# keypad.net
KiCad netlist of a schematic drawn in Altium Designer
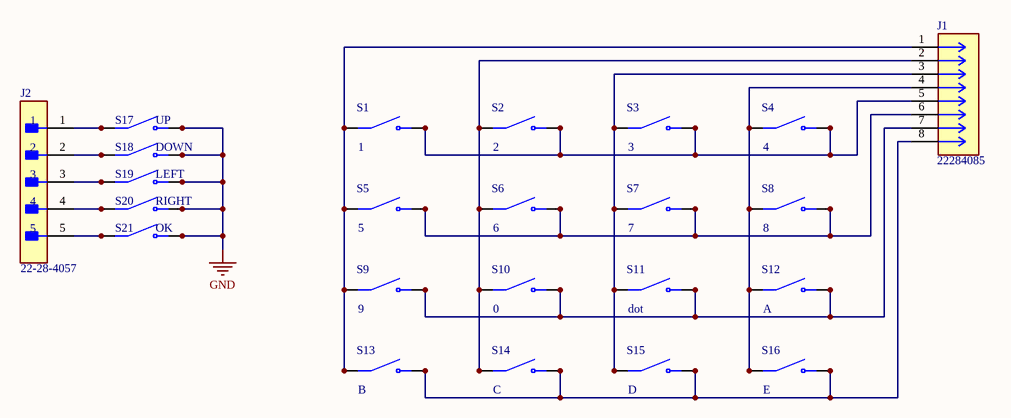
[diagram p0: keypad.SchDoc]

(export (version "E")
  (design (tool "Eeschema 10.0.6"))
  (components
    (comp (ref "J1")
      (value "22284085")
      (footprint "CONN_SD-42375-001_M295_08_MOL")
      (libsource (lib "Achintha Bandara") (part "22284085"))
    )
    (comp (ref "J2")
      (value "22-28-4057")
      (footprint "FP-22-28-4057-MFG")
      (description "KK 100 HDR ASSY BKWY 05 CKT 30 S")
      (libsource (lib "Altium Content Vault") (part "bf93c07fd2649a848d0ec8585582aab"))
    )
    (comp (ref "S1")
      (value "1")
      (footprint "SW_B3F-4050")
      (description "Tactile Switch SPST-NO Top Actuated Through Hole")
      (fields (field (name "MP") "B3F-4050") (field (name "MF") "Omron Electronics"))
      (libsource (lib "Achintha Bandara") (part "B3F-4050"))
    )
    (comp (ref "S2")
      (value "2")
      (footprint "SW_B3F-4050")
      (description "Tactile Switch SPST-NO Top Actuated Through Hole")
      (fields (field (name "MP") "B3F-4050") (field (name "MF") "Omron Electronics"))
      (libsource (lib "Achintha Bandara") (part "B3F-4050"))
    )
    (comp (ref "S3")
      (value "3")
      (footprint "SW_B3F-4050")
      (description "Tactile Switch SPST-NO Top Actuated Through Hole")
      (fields (field (name "MP") "B3F-4050") (field (name "MF") "Omron Electronics"))
      (libsource (lib "Achintha Bandara") (part "B3F-4050"))
    )
    (comp (ref "S4")
      (value "4")
      (footprint "SW_B3F-4050")
      (description "Tactile Switch SPST-NO Top Actuated Through Hole")
      (fields (field (name "MP") "B3F-4050") (field (name "MF") "Omron Electronics"))
      (libsource (lib "Achintha Bandara") (part "B3F-4050"))
    )
    (comp (ref "S5")
      (value "5")
      (footprint "SW_B3F-4050")
      (description "Tactile Switch SPST-NO Top Actuated Through Hole")
      (fields (field (name "MP") "B3F-4050") (field (name "MF") "Omron Electronics"))
      (libsource (lib "Achintha Bandara") (part "B3F-4050"))
    )
    (comp (ref "S6")
      (value "6")
      (footprint "SW_B3F-4050")
      (description "Tactile Switch SPST-NO Top Actuated Through Hole")
      (fields (field (name "MP") "B3F-4050") (field (name "MF") "Omron Electronics"))
      (libsource (lib "Achintha Bandara") (part "B3F-4050"))
    )
    (comp (ref "S7")
      (value "7")
      (footprint "SW_B3F-4050")
      (description "Tactile Switch SPST-NO Top Actuated Through Hole")
      (fields (field (name "MP") "B3F-4050") (field (name "MF") "Omron Electronics"))
      (libsource (lib "Achintha Bandara") (part "B3F-4050"))
    )
    (comp (ref "S8")
      (value "8")
      (footprint "SW_B3F-4050")
      (description "Tactile Switch SPST-NO Top Actuated Through Hole")
      (fields (field (name "MP") "B3F-4050") (field (name "MF") "Omron Electronics"))
      (libsource (lib "Achintha Bandara") (part "B3F-4050"))
    )
    (comp (ref "S9")
      (value "9")
      (footprint "SW_B3F-4050")
      (description "Tactile Switch SPST-NO Top Actuated Through Hole")
      (fields (field (name "MP") "B3F-4050") (field (name "MF") "Omron Electronics"))
      (libsource (lib "Achintha Bandara") (part "B3F-4050"))
    )
    (comp (ref "S10")
      (value "0")
      (footprint "SW_B3F-4050")
      (description "Tactile Switch SPST-NO Top Actuated Through Hole")
      (fields (field (name "MP") "B3F-4050") (field (name "MF") "Omron Electronics"))
      (libsource (lib "Achintha Bandara") (part "B3F-4050"))
    )
    (comp (ref "S11")
      (value "dot")
      (footprint "SW_B3F-4050")
      (description "Tactile Switch SPST-NO Top Actuated Through Hole")
      (fields (field (name "MP") "B3F-4050") (field (name "MF") "Omron Electronics"))
      (libsource (lib "Achintha Bandara") (part "B3F-4050"))
    )
    (comp (ref "S12")
      (value "A")
      (footprint "SW_B3F-4050")
      (description "Tactile Switch SPST-NO Top Actuated Through Hole")
      (fields (field (name "MP") "B3F-4050") (field (name "MF") "Omron Electronics"))
      (libsource (lib "Achintha Bandara") (part "B3F-4050"))
    )
    (comp (ref "S13")
      (value "B")
      (footprint "SW_B3F-4050")
      (description "Tactile Switch SPST-NO Top Actuated Through Hole")
      (fields (field (name "MP") "B3F-4050") (field (name "MF") "Omron Electronics"))
      (libsource (lib "Achintha Bandara") (part "B3F-4050"))
    )
    (comp (ref "S14")
      (value "C")
      (footprint "SW_B3F-4050")
      (description "Tactile Switch SPST-NO Top Actuated Through Hole")
      (fields (field (name "MP") "B3F-4050") (field (name "MF") "Omron Electronics"))
      (libsource (lib "Achintha Bandara") (part "B3F-4050"))
    )
    (comp (ref "S15")
      (value "D")
      (footprint "SW_B3F-4050")
      (description "Tactile Switch SPST-NO Top Actuated Through Hole")
      (fields (field (name "MP") "B3F-4050") (field (name "MF") "Omron Electronics"))
      (libsource (lib "Achintha Bandara") (part "B3F-4050"))
    )
    (comp (ref "S16")
      (value "E")
      (footprint "SW_B3F-4050")
      (description "Tactile Switch SPST-NO Top Actuated Through Hole")
      (fields (field (name "MP") "B3F-4050") (field (name "MF") "Omron Electronics"))
      (libsource (lib "Achintha Bandara") (part "B3F-4050"))
    )
    (comp (ref "S17")
      (value "UP")
      (footprint "SW_B3F-4050")
      (description "Tactile Switch SPST-NO Top Actuated Through Hole")
      (fields (field (name "MP") "B3F-4050") (field (name "MF") "Omron Electronics"))
      (libsource (lib "Achintha Bandara") (part "B3F-4050"))
    )
    (comp (ref "S18")
      (value "DOWN")
      (footprint "SW_B3F-4050")
      (description "Tactile Switch SPST-NO Top Actuated Through Hole")
      (fields (field (name "MP") "B3F-4050") (field (name "MF") "Omron Electronics"))
      (libsource (lib "Achintha Bandara") (part "B3F-4050"))
    )
    (comp (ref "S19")
      (value "LEFT")
      (footprint "SW_B3F-4050")
      (description "Tactile Switch SPST-NO Top Actuated Through Hole")
      (fields (field (name "MP") "B3F-4050") (field (name "MF") "Omron Electronics"))
      (libsource (lib "Achintha Bandara") (part "B3F-4050"))
    )
    (comp (ref "S20")
      (value "RIGHT")
      (footprint "SW_B3F-4050")
      (description "Tactile Switch SPST-NO Top Actuated Through Hole")
      (fields (field (name "MP") "B3F-4050") (field (name "MF") "Omron Electronics"))
      (libsource (lib "Achintha Bandara") (part "B3F-4050"))
    )
    (comp (ref "S21")
      (value "OK")
      (footprint "SW_B3F-4050")
      (description "Tactile Switch SPST-NO Top Actuated Through Hole")
      (fields (field (name "MP") "B3F-4050") (field (name "MF") "Omron Electronics"))
      (libsource (lib "Achintha Bandara") (part "B3F-4050"))
    )
  )
  (nets
    (net (code "1") (name "GND") (class "Default")
      (node (ref "S17") (pin "3") (pinfunction "NO_3") (pintype "passive"))
      (node (ref "S17") (pin "4") (pinfunction "NO_4") (pintype "passive"))
      (node (ref "S18") (pin "3") (pinfunction "NO_3") (pintype "passive"))
      (node (ref "S18") (pin "4") (pinfunction "NO_4") (pintype "passive"))
      (node (ref "S19") (pin "3") (pinfunction "NO_3") (pintype "passive"))
      (node (ref "S19") (pin "4") (pinfunction "NO_4") (pintype "passive"))
      (node (ref "S20") (pin "3") (pinfunction "NO_3") (pintype "passive"))
      (node (ref "S20") (pin "4") (pinfunction "NO_4") (pintype "passive"))
      (node (ref "S21") (pin "3") (pinfunction "NO_3") (pintype "passive"))
      (node (ref "S21") (pin "4") (pinfunction "NO_4") (pintype "passive"))
    )
    (net (code "2") (name "Net-(J1-Pad1)") (class "Default")
      (node (ref "J1") (pin "1") (pinfunction "1_1") (pintype "passive"))
      (node (ref "S1") (pin "1") (pinfunction "COM_1") (pintype "passive"))
      (node (ref "S1") (pin "2") (pinfunction "COM_2") (pintype "passive"))
      (node (ref "S13") (pin "1") (pinfunction "COM_1") (pintype "passive"))
      (node (ref "S13") (pin "2") (pinfunction "COM_2") (pintype "passive"))
      (node (ref "S5") (pin "1") (pinfunction "COM_1") (pintype "passive"))
      (node (ref "S5") (pin "2") (pinfunction "COM_2") (pintype "passive"))
      (node (ref "S9") (pin "1") (pinfunction "COM_1") (pintype "passive"))
      (node (ref "S9") (pin "2") (pinfunction "COM_2") (pintype "passive"))
    )
    (net (code "3") (name "Net-(J1-Pad2)") (class "Default")
      (node (ref "J1") (pin "2") (pinfunction "2_2") (pintype "passive"))
      (node (ref "S10") (pin "1") (pinfunction "COM_1") (pintype "passive"))
      (node (ref "S10") (pin "2") (pinfunction "COM_2") (pintype "passive"))
      (node (ref "S14") (pin "1") (pinfunction "COM_1") (pintype "passive"))
      (node (ref "S14") (pin "2") (pinfunction "COM_2") (pintype "passive"))
      (node (ref "S2") (pin "1") (pinfunction "COM_1") (pintype "passive"))
      (node (ref "S2") (pin "2") (pinfunction "COM_2") (pintype "passive"))
      (node (ref "S6") (pin "1") (pinfunction "COM_1") (pintype "passive"))
      (node (ref "S6") (pin "2") (pinfunction "COM_2") (pintype "passive"))
    )
    (net (code "4") (name "Net-(J1-Pad3)") (class "Default")
      (node (ref "J1") (pin "3") (pinfunction "3_3") (pintype "passive"))
      (node (ref "S11") (pin "1") (pinfunction "COM_1") (pintype "passive"))
      (node (ref "S11") (pin "2") (pinfunction "COM_2") (pintype "passive"))
      (node (ref "S15") (pin "1") (pinfunction "COM_1") (pintype "passive"))
      (node (ref "S15") (pin "2") (pinfunction "COM_2") (pintype "passive"))
      (node (ref "S3") (pin "1") (pinfunction "COM_1") (pintype "passive"))
      (node (ref "S3") (pin "2") (pinfunction "COM_2") (pintype "passive"))
      (node (ref "S7") (pin "1") (pinfunction "COM_1") (pintype "passive"))
      (node (ref "S7") (pin "2") (pinfunction "COM_2") (pintype "passive"))
    )
    (net (code "5") (name "Net-(J1-Pad4)") (class "Default")
      (node (ref "J1") (pin "4") (pinfunction "4_4") (pintype "passive"))
      (node (ref "S12") (pin "1") (pinfunction "COM_1") (pintype "passive"))
      (node (ref "S12") (pin "2") (pinfunction "COM_2") (pintype "passive"))
      (node (ref "S16") (pin "1") (pinfunction "COM_1") (pintype "passive"))
      (node (ref "S16") (pin "2") (pinfunction "COM_2") (pintype "passive"))
      (node (ref "S4") (pin "1") (pinfunction "COM_1") (pintype "passive"))
      (node (ref "S4") (pin "2") (pinfunction "COM_2") (pintype "passive"))
      (node (ref "S8") (pin "1") (pinfunction "COM_1") (pintype "passive"))
      (node (ref "S8") (pin "2") (pinfunction "COM_2") (pintype "passive"))
    )
    (net (code "6") (name "Net-(J1-Pad5)") (class "Default")
      (node (ref "J1") (pin "5") (pinfunction "5_5") (pintype "passive"))
      (node (ref "S1") (pin "3") (pinfunction "NO_3") (pintype "passive"))
      (node (ref "S1") (pin "4") (pinfunction "NO_4") (pintype "passive"))
      (node (ref "S2") (pin "3") (pinfunction "NO_3") (pintype "passive"))
      (node (ref "S2") (pin "4") (pinfunction "NO_4") (pintype "passive"))
      (node (ref "S3") (pin "3") (pinfunction "NO_3") (pintype "passive"))
      (node (ref "S3") (pin "4") (pinfunction "NO_4") (pintype "passive"))
      (node (ref "S4") (pin "3") (pinfunction "NO_3") (pintype "passive"))
      (node (ref "S4") (pin "4") (pinfunction "NO_4") (pintype "passive"))
    )
    (net (code "7") (name "Net-(J1-Pad6)") (class "Default")
      (node (ref "J1") (pin "6") (pinfunction "6_6") (pintype "passive"))
      (node (ref "S5") (pin "3") (pinfunction "NO_3") (pintype "passive"))
      (node (ref "S5") (pin "4") (pinfunction "NO_4") (pintype "passive"))
      (node (ref "S6") (pin "3") (pinfunction "NO_3") (pintype "passive"))
      (node (ref "S6") (pin "4") (pinfunction "NO_4") (pintype "passive"))
      (node (ref "S7") (pin "3") (pinfunction "NO_3") (pintype "passive"))
      (node (ref "S7") (pin "4") (pinfunction "NO_4") (pintype "passive"))
      (node (ref "S8") (pin "3") (pinfunction "NO_3") (pintype "passive"))
      (node (ref "S8") (pin "4") (pinfunction "NO_4") (pintype "passive"))
    )
    (net (code "8") (name "Net-(J1-Pad7)") (class "Default")
      (node (ref "J1") (pin "7") (pinfunction "7_7") (pintype "passive"))
      (node (ref "S10") (pin "3") (pinfunction "NO_3") (pintype "passive"))
      (node (ref "S10") (pin "4") (pinfunction "NO_4") (pintype "passive"))
      (node (ref "S11") (pin "3") (pinfunction "NO_3") (pintype "passive"))
      (node (ref "S11") (pin "4") (pinfunction "NO_4") (pintype "passive"))
      (node (ref "S12") (pin "3") (pinfunction "NO_3") (pintype "passive"))
      (node (ref "S12") (pin "4") (pinfunction "NO_4") (pintype "passive"))
      (node (ref "S9") (pin "3") (pinfunction "NO_3") (pintype "passive"))
      (node (ref "S9") (pin "4") (pinfunction "NO_4") (pintype "passive"))
    )
    (net (code "9") (name "Net-(J1-Pad8)") (class "Default")
      (node (ref "J1") (pin "8") (pinfunction "8_8") (pintype "passive"))
      (node (ref "S13") (pin "3") (pinfunction "NO_3") (pintype "passive"))
      (node (ref "S13") (pin "4") (pinfunction "NO_4") (pintype "passive"))
      (node (ref "S14") (pin "3") (pinfunction "NO_3") (pintype "passive"))
      (node (ref "S14") (pin "4") (pinfunction "NO_4") (pintype "passive"))
      (node (ref "S15") (pin "3") (pinfunction "NO_3") (pintype "passive"))
      (node (ref "S15") (pin "4") (pinfunction "NO_4") (pintype "passive"))
      (node (ref "S16") (pin "3") (pinfunction "NO_3") (pintype "passive"))
      (node (ref "S16") (pin "4") (pinfunction "NO_4") (pintype "passive"))
    )
    (net (code "10") (name "Net-(J2-Pad1)") (class "Default")
      (node (ref "J2") (pin "1") (pinfunction "1_1") (pintype "passive"))
      (node (ref "S17") (pin "1") (pinfunction "COM_1") (pintype "passive"))
      (node (ref "S17") (pin "2") (pinfunction "COM_2") (pintype "passive"))
    )
    (net (code "11") (name "Net-(J2-Pad2)") (class "Default")
      (node (ref "J2") (pin "2") (pinfunction "2_2") (pintype "passive"))
      (node (ref "S18") (pin "1") (pinfunction "COM_1") (pintype "passive"))
      (node (ref "S18") (pin "2") (pinfunction "COM_2") (pintype "passive"))
    )
    (net (code "12") (name "Net-(J2-Pad3)") (class "Default")
      (node (ref "J2") (pin "3") (pinfunction "3_3") (pintype "passive"))
      (node (ref "S19") (pin "1") (pinfunction "COM_1") (pintype "passive"))
      (node (ref "S19") (pin "2") (pinfunction "COM_2") (pintype "passive"))
    )
    (net (code "13") (name "Net-(J2-Pad4)") (class "Default")
      (node (ref "J2") (pin "4") (pinfunction "4_4") (pintype "passive"))
      (node (ref "S20") (pin "1") (pinfunction "COM_1") (pintype "passive"))
      (node (ref "S20") (pin "2") (pinfunction "COM_2") (pintype "passive"))
    )
    (net (code "14") (name "Net-(J2-Pad5)") (class "Default")
      (node (ref "J2") (pin "5") (pinfunction "5_5") (pintype "passive"))
      (node (ref "S21") (pin "1") (pinfunction "COM_1") (pintype "passive"))
      (node (ref "S21") (pin "2") (pinfunction "COM_2") (pintype "passive"))
    )
  )
)
